# TOP.net
KiCad netlist of a schematic drawn in Altium Designer
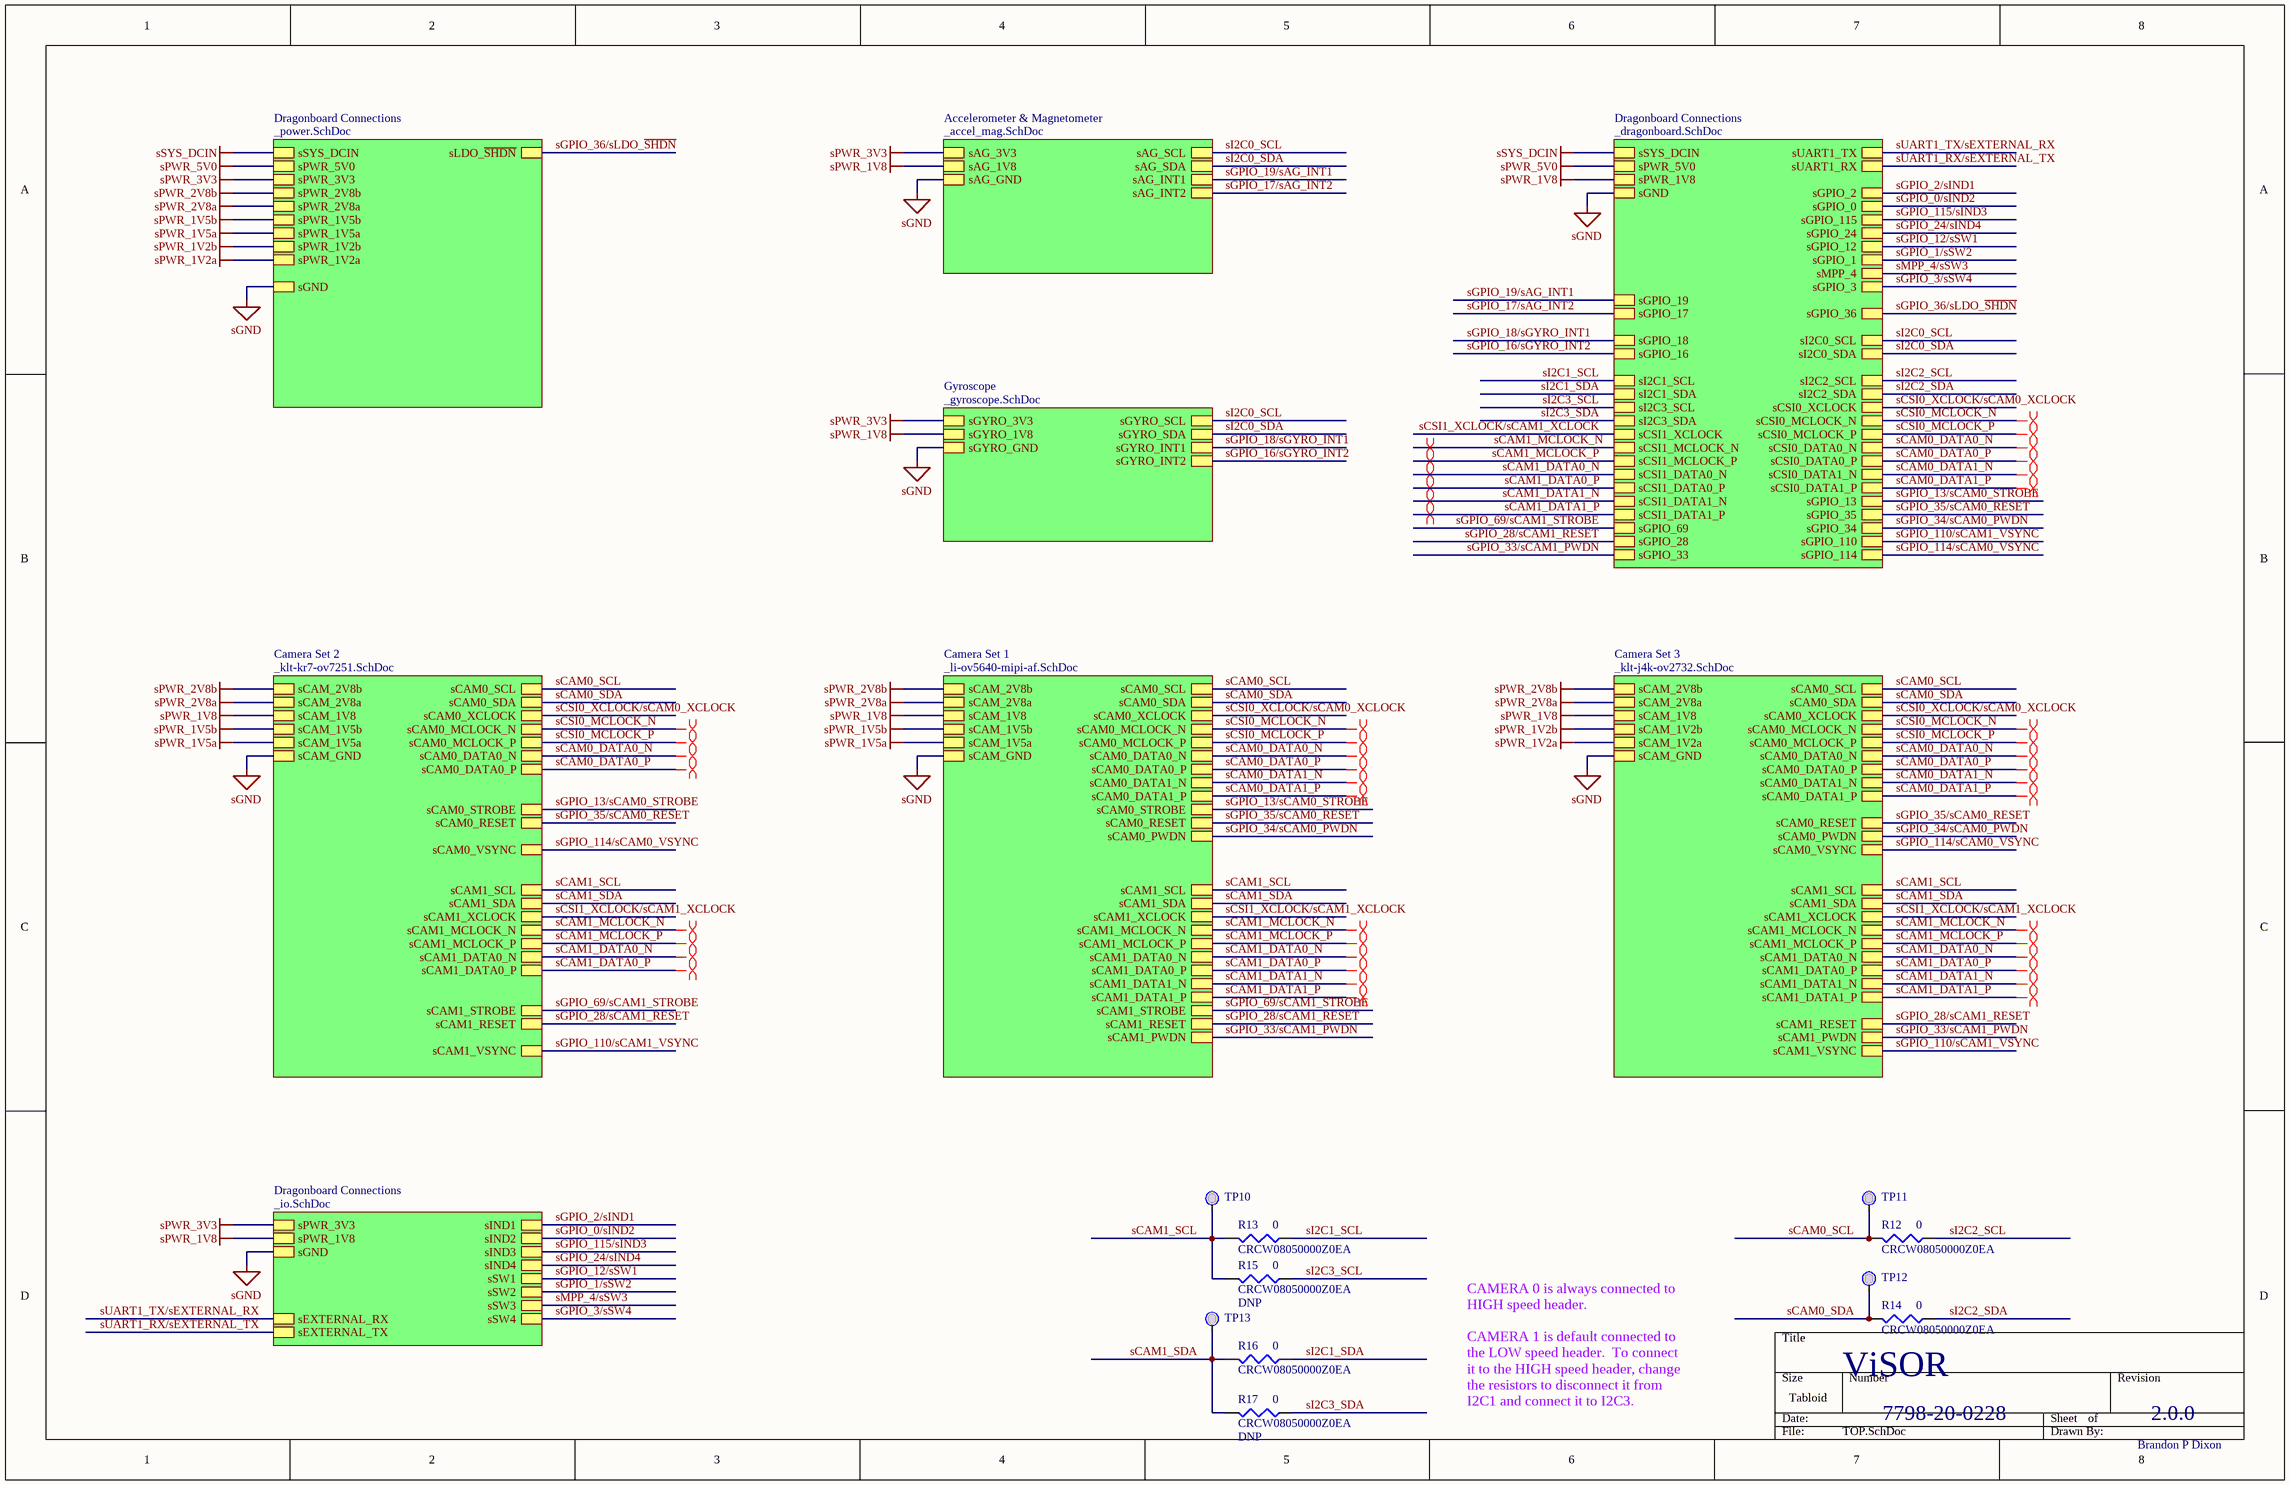
[diagram p0: TOP.SchDoc]

(export (version "E")
  (design (tool "Eeschema 10.0.6"))
  (components
    (comp (ref "R12")
      (value "CRCW08050000Z0EA")
      (footprint "6-0805_M")
      (description "0Ω Resistor")
      (fields (field (name "ALTIUM_VALUE") "0") (field (name "PUBLISHER") "Altium Limited"))
      (libsource (lib "miscellaneous_devices") (part "Res3"))
    )
    (comp (ref "R13")
      (value "CRCW08050000Z0EA")
      (footprint "6-0805_M")
      (description "0Ω Resistor")
      (fields (field (name "ALTIUM_VALUE") "0") (field (name "PUBLISHER") "Altium Limited"))
      (libsource (lib "miscellaneous_devices") (part "Res3"))
    )
    (comp (ref "R14")
      (value "CRCW08050000Z0EA")
      (footprint "6-0805_M")
      (description "0Ω Resistor")
      (fields (field (name "ALTIUM_VALUE") "0") (field (name "PUBLISHER") "Altium Limited"))
      (libsource (lib "miscellaneous_devices") (part "Res3"))
    )
    (comp (ref "R15")
      (value "CRCW08050000Z0EA")
      (footprint "6-0805_M")
      (description "0Ω Resistor")
      (fields
        (field (name "ALTIUM_VALUE") "0")
        (field (name "ALTIUM_UNNAMED_1") "DNP")
        (field (name "PUBLISHER") "Altium Limited")
      )
      (libsource (lib "miscellaneous_devices") (part "Res3"))
    )
    (comp (ref "R16")
      (value "CRCW08050000Z0EA")
      (footprint "6-0805_M")
      (description "0Ω Resistor")
      (fields (field (name "ALTIUM_VALUE") "0") (field (name "PUBLISHER") "Altium Limited"))
      (libsource (lib "miscellaneous_devices") (part "Res3"))
    )
    (comp (ref "R17")
      (value "CRCW08050000Z0EA")
      (footprint "6-0805_M")
      (description "0Ω Resistor")
      (fields
        (field (name "ALTIUM_VALUE") "0")
        (field (name "ALTIUM_UNNAMED_1") "DNP")
        (field (name "PUBLISHER") "Altium Limited")
      )
      (libsource (lib "miscellaneous_devices") (part "Res3"))
    )
    (comp (ref "TP10") (value "TP") (footprint "TP_TH") (libsource (lib "common") (part "TP")))
    (comp (ref "TP11") (value "TP") (footprint "TP_TH") (libsource (lib "common") (part "TP")))
    (comp (ref "TP12") (value "TP") (footprint "TP_TH") (libsource (lib "common") (part "TP")))
    (comp (ref "TP13") (value "TP") (footprint "TP_TH") (libsource (lib "common") (part "TP")))
  )
  (nets
    (net (code "5") (name "/sCAM0_SCL") (class "Default")
      (node (ref "R12") (pin "2") (pinfunction "2_2") (pintype "passive"))
      (node (ref "TP11") (pin "1") (pinfunction "1_1") (pintype "passive"))
    )
    (net (code "6") (name "/sCAM0_SDA") (class "Default")
      (node (ref "R14") (pin "2") (pinfunction "2_2") (pintype "passive"))
      (node (ref "TP12") (pin "1") (pinfunction "1_1") (pintype "passive"))
    )
    (net (code "13") (name "/sCAM1_SCL") (class "Default")
      (node (ref "R13") (pin "2") (pinfunction "2_2") (pintype "passive"))
      (node (ref "R15") (pin "2") (pinfunction "2_2") (pintype "passive"))
      (node (ref "TP10") (pin "1") (pinfunction "1_1") (pintype "passive"))
    )
    (net (code "14") (name "/sCAM1_SDA") (class "Default")
      (node (ref "R16") (pin "2") (pinfunction "2_2") (pintype "passive"))
      (node (ref "R17") (pin "2") (pinfunction "2_2") (pintype "passive"))
      (node (ref "TP13") (pin "1") (pinfunction "1_1") (pintype "passive"))
    )
    (net (code "41") (name "/sI2C1_SCL") (class "Default")
      (node (ref "R13") (pin "1") (pinfunction "1_1") (pintype "passive"))
    )
    (net (code "42") (name "/sI2C1_SDA") (class "Default")
      (node (ref "R16") (pin "1") (pinfunction "1_1") (pintype "passive"))
    )
    (net (code "43") (name "/sI2C2_SCL") (class "Default")
      (node (ref "R12") (pin "1") (pinfunction "1_1") (pintype "passive"))
    )
    (net (code "44") (name "/sI2C2_SDA") (class "Default")
      (node (ref "R14") (pin "1") (pinfunction "1_1") (pintype "passive"))
    )
    (net (code "45") (name "/sI2C3_SCL") (class "Default")
      (node (ref "R15") (pin "1") (pinfunction "1_1") (pintype "passive"))
    )
    (net (code "46") (name "/sI2C3_SDA") (class "Default")
      (node (ref "R17") (pin "1") (pinfunction "1_1") (pintype "passive"))
    )
  )
)
